# Sheet1.net
KiCad netlist of a schematic drawn in Altium Designer
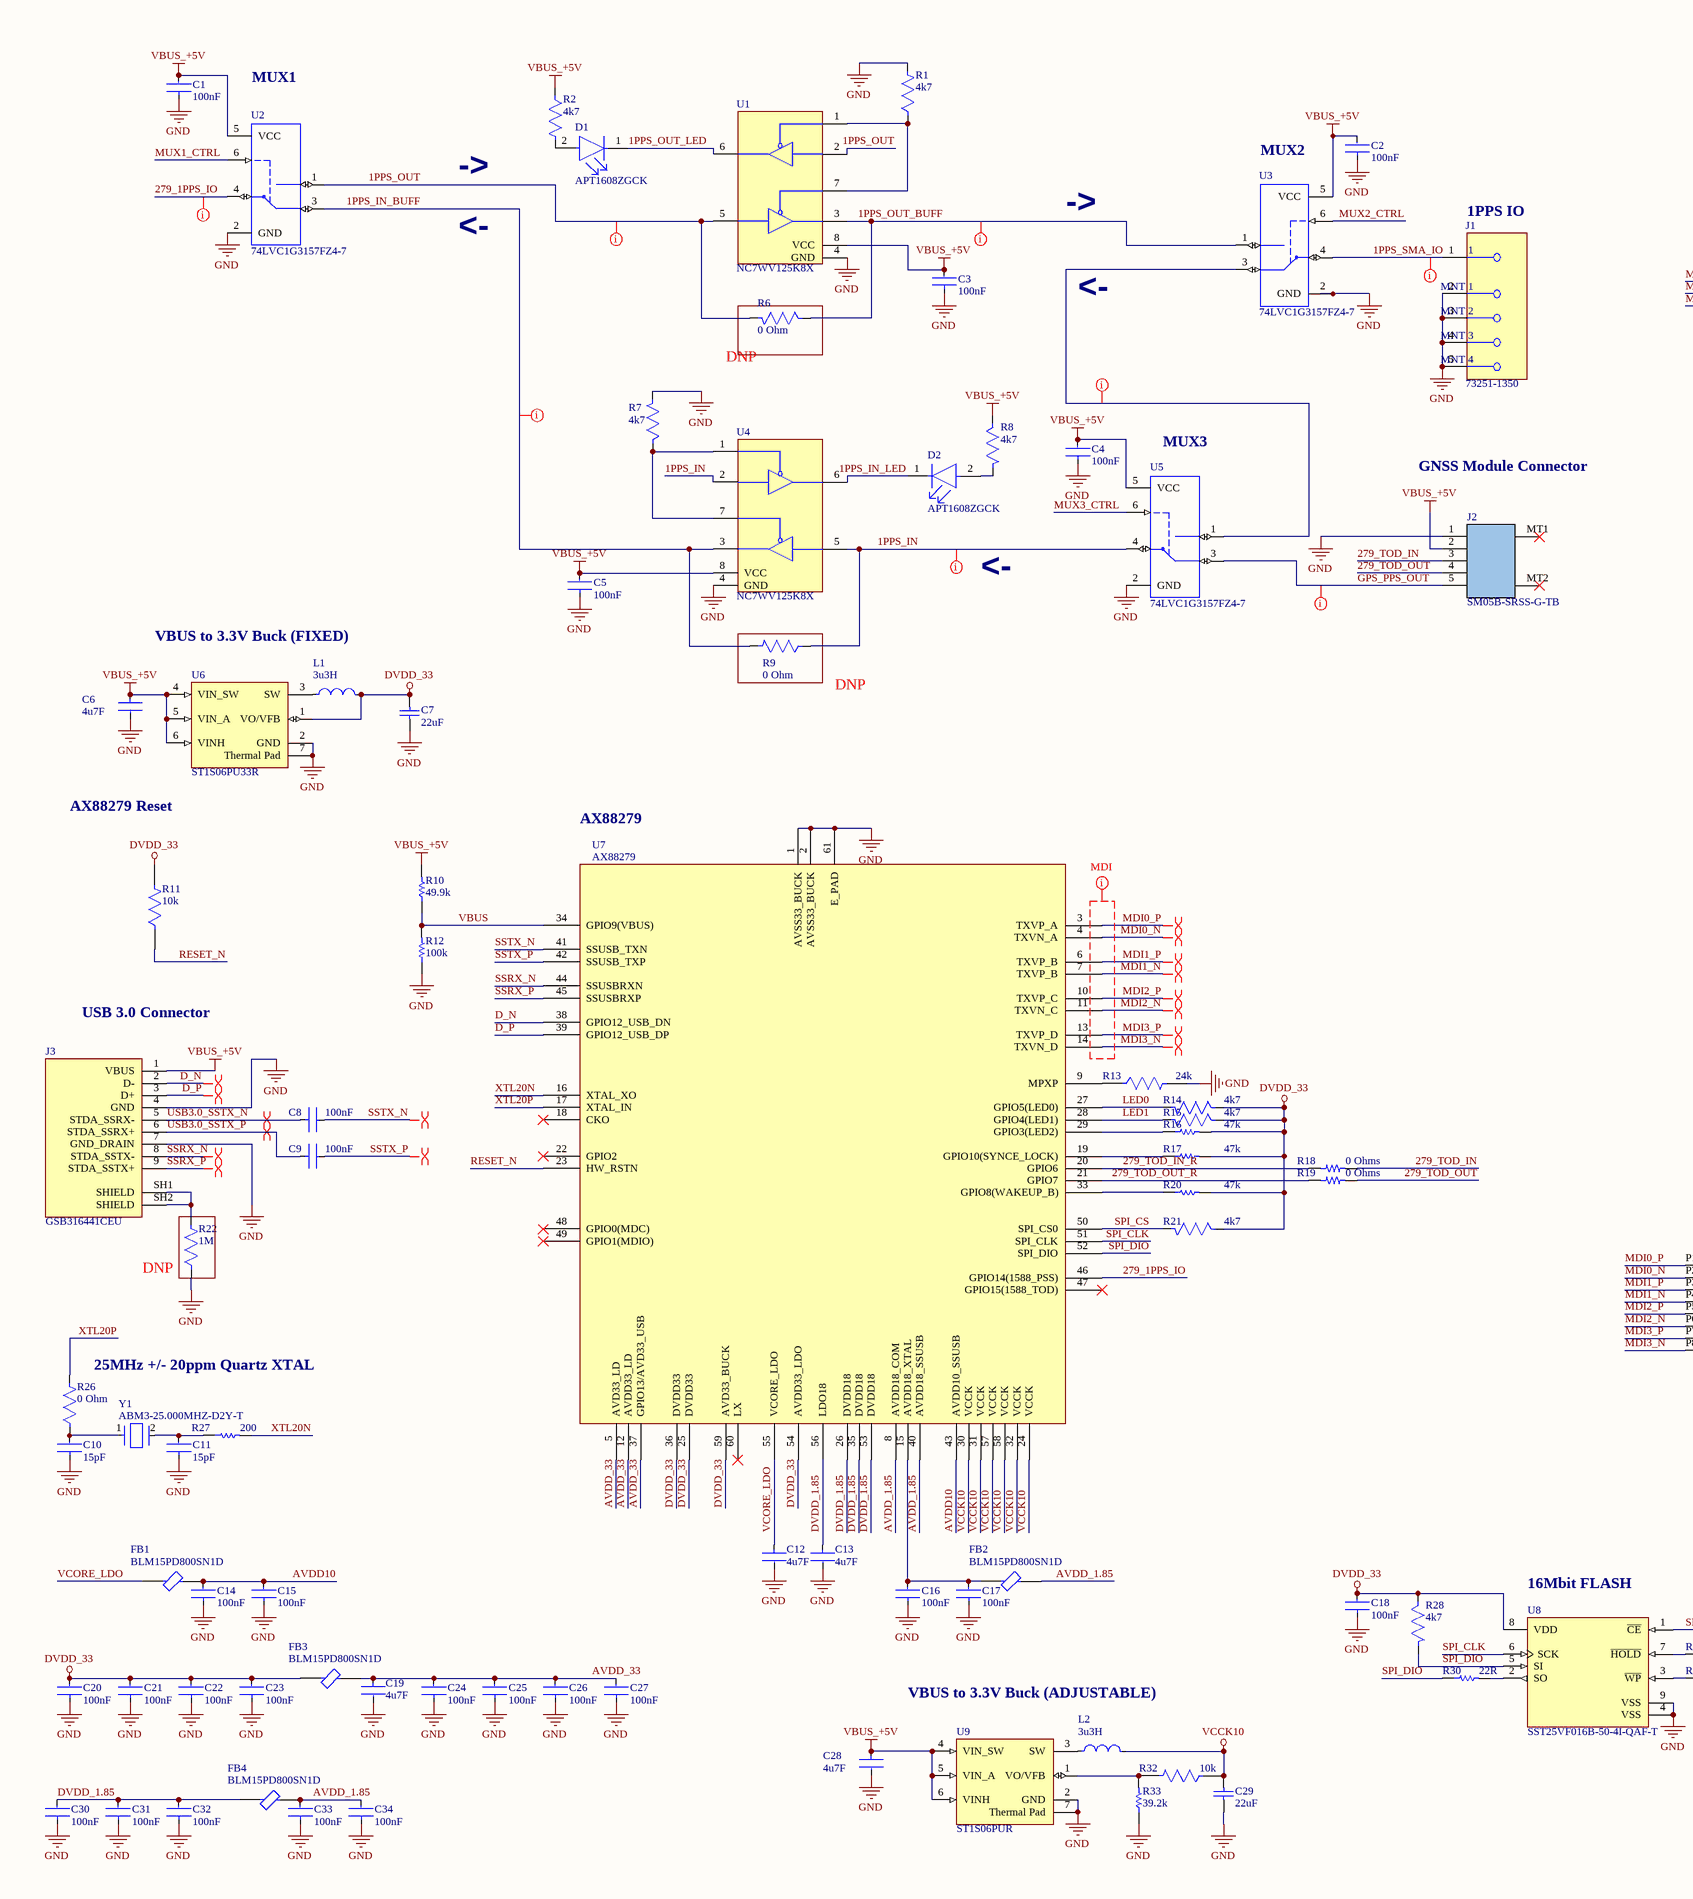
[diagram p0: Sheet1.SchDoc, left]
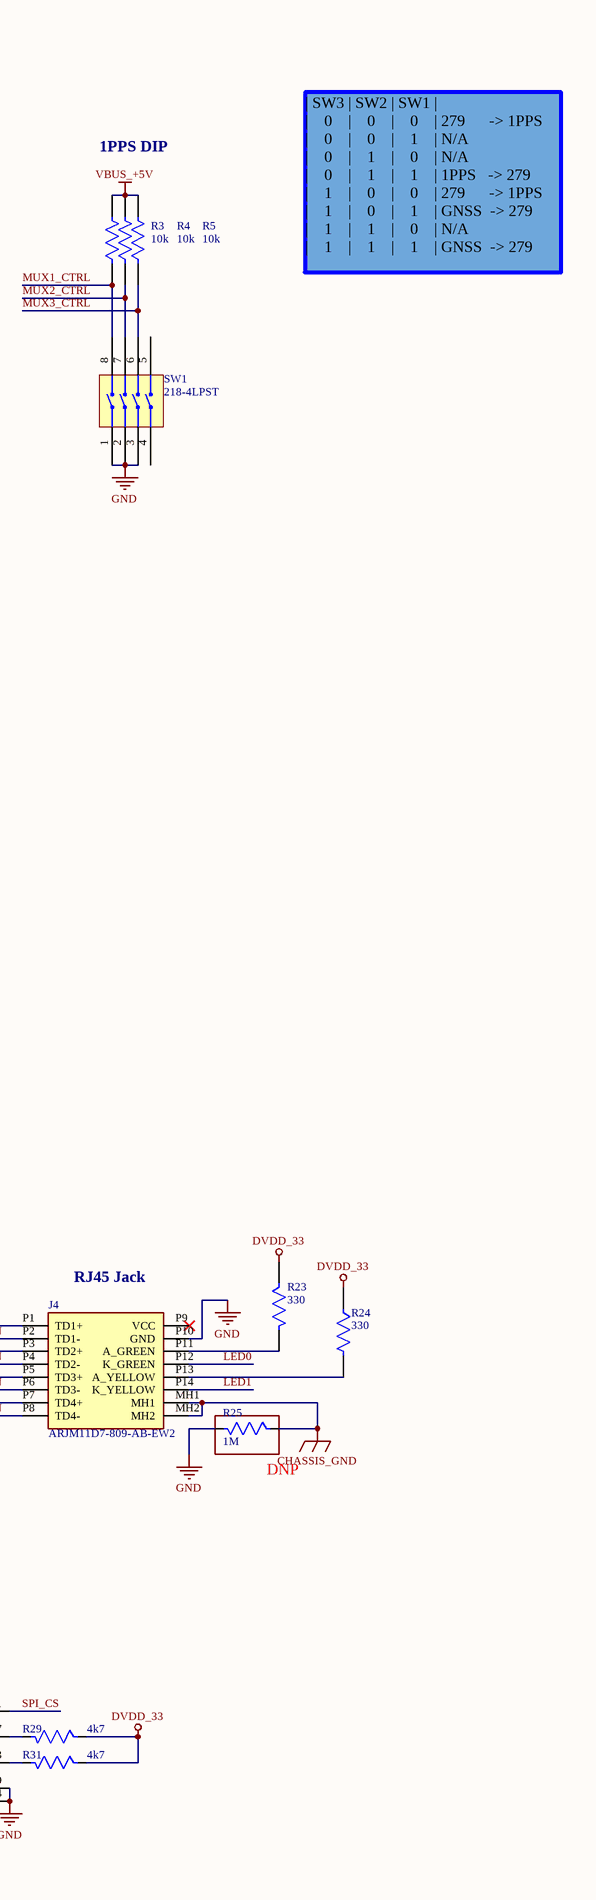
[diagram p1: Sheet1.SchDoc, right]

(export (version "E")
  (design (tool "Eeschema 10.0.6"))
  (components
    (comp (ref "C1")
      (value "100nF")
      (footprint "FP-CL251-IPC_C")
      (description "Cap Ceramic 100nF 10V X7R ±10% SMD 0402 +125°C Paper T/R")
      (fields (field (name "TOLERANCE") "10%") (field (name "MANUFACTURER") "KEMET"))
      (libsource (lib "Altium Content Vault") (part "b4654b650e69147ec39a6b967a45e02"))
    )
    (comp (ref "C2")
      (value "100nF")
      (footprint "FP-CL251-IPC_C")
      (description "Cap Ceramic 100nF 10V X7R ±10% SMD 0402 +125°C Paper T/R")
      (fields (field (name "TOLERANCE") "10%") (field (name "MANUFACTURER") "KEMET"))
      (libsource (lib "Altium Content Vault") (part "b4654b650e69147ec39a6b967a45e02"))
    )
    (comp (ref "C3")
      (value "100nF")
      (footprint "FP-CL251-IPC_C")
      (description "Cap Ceramic 100nF 10V X7R ±10% SMD 0402 +125°C Paper T/R")
      (fields (field (name "TOLERANCE") "10%") (field (name "MANUFACTURER") "KEMET"))
      (libsource (lib "Altium Content Vault") (part "b4654b650e69147ec39a6b967a45e02"))
    )
    (comp (ref "C4")
      (value "100nF")
      (footprint "FP-CL251-IPC_C")
      (description "Cap Ceramic 100nF 10V X7R ±10% SMD 0402 +125°C Paper T/R")
      (fields (field (name "TOLERANCE") "10%") (field (name "MANUFACTURER") "KEMET"))
      (libsource (lib "Altium Content Vault") (part "b4654b650e69147ec39a6b967a45e02"))
    )
    (comp (ref "C5")
      (value "100nF")
      (footprint "FP-CL251-IPC_C")
      (description "Cap Ceramic 100nF 10V X7R ±10% SMD 0402 +125°C Paper T/R")
      (fields (field (name "TOLERANCE") "10%") (field (name "MANUFACTURER") "KEMET"))
      (libsource (lib "Altium Content Vault") (part "b4654b650e69147ec39a6b967a45e02"))
    )
    (comp (ref "C6")
      (value "4u7F")
      (footprint "FP-0402-L_1_0_0_15-W_0_5-IPC_C")
      (description "Ceramic Capacitor General Use 4.7uF ±20% 10V X5R 0402")
      (fields (field (name "TOLERANCE") "20%") (field (name "MANUFACTURER") "Taiyo Yuden"))
      (libsource (lib "Altium Content Vault") (part "236180d848d6139a670b325ea6854c9"))
    )
    (comp (ref "C7")
      (value "22uF")
      (footprint "CAPC1608X100X20ML10")
      (description "Chip Capacitor, 22 uF, +/- 20%, 10 V, -55 to 85 degC, 0603 (1608 Metric), RoHS, Tape and Reel")
      (fields (field (name "MANUFACTURER") "TDK") (field (name "TOLERANCE") "±20%"))
      (libsource (lib "Altium Content Vault") (part "CAP-NP-2"))
    )
    (comp (ref "C8")
      (value "100nF")
      (footprint "FP-CL251-IPC_C")
      (description "Cap Ceramic 100nF 10V X7R ±10% SMD 0402 +125°C Paper T/R")
      (fields (field (name "TOLERANCE") "10%") (field (name "MANUFACTURER") "KEMET"))
      (libsource (lib "Altium Content Vault") (part "b4654b650e69147ec39a6b967a45e02"))
    )
    (comp (ref "C9")
      (value "100nF")
      (footprint "FP-CL251-IPC_C")
      (description "Cap Ceramic 100nF 10V X7R ±10% SMD 0402 +125°C Paper T/R")
      (fields (field (name "TOLERANCE") "10%") (field (name "MANUFACTURER") "KEMET"))
      (libsource (lib "Altium Content Vault") (part "b4654b650e69147ec39a6b967a45e02"))
    )
    (comp (ref "C10")
      (value "15pF")
      (footprint "FP-CBR04C-MFG")
      (description "CAP CER 15PF 100V C0G/NP0 0402")
      (fields
        (field (name "MANUFACTURER") "KEMET")
        (field (name "OCTOPART") "https://octopart.com/cbr04c150f1gac-kemet-30609229")
      )
      (libsource (lib "Altium Content Vault") (part "236180d848d6139a670b325ea6854c9"))
    )
    (comp (ref "C11")
      (value "15pF")
      (footprint "FP-CBR04C-MFG")
      (description "CAP CER 15PF 100V C0G/NP0 0402")
      (fields
        (field (name "MANUFACTURER") "KEMET")
        (field (name "OCTOPART") "https://octopart.com/cbr04c150f1gac-kemet-30609229")
      )
      (libsource (lib "Altium Content Vault") (part "236180d848d6139a670b325ea6854c9"))
    )
    (comp (ref "C12")
      (value "4u7F")
      (footprint "FP-0402-L_1_0_0_15-W_0_5-IPC_C")
      (description "Ceramic Capacitor General Use 4.7uF ±20% 10V X5R 0402")
      (fields (field (name "TOLERANCE") "20%") (field (name "MANUFACTURER") "Taiyo Yuden"))
      (libsource (lib "Altium Content Vault") (part "236180d848d6139a670b325ea6854c9"))
    )
    (comp (ref "C13")
      (value "4u7F")
      (footprint "FP-0402-L_1_0_0_15-W_0_5-IPC_C")
      (description "Ceramic Capacitor General Use 4.7uF ±20% 10V X5R 0402")
      (fields (field (name "TOLERANCE") "20%") (field (name "MANUFACTURER") "Taiyo Yuden"))
      (libsource (lib "Altium Content Vault") (part "236180d848d6139a670b325ea6854c9"))
    )
    (comp (ref "C14")
      (value "100nF")
      (footprint "FP-CL251-IPC_C")
      (description "Cap Ceramic 100nF 10V X7R ±10% SMD 0402 +125°C Paper T/R")
      (fields (field (name "TOLERANCE") "10%") (field (name "MANUFACTURER") "KEMET"))
      (libsource (lib "Altium Content Vault") (part "b4654b650e69147ec39a6b967a45e02"))
    )
    (comp (ref "C15")
      (value "100nF")
      (footprint "FP-CL251-IPC_C")
      (description "Cap Ceramic 100nF 10V X7R ±10% SMD 0402 +125°C Paper T/R")
      (fields (field (name "TOLERANCE") "10%") (field (name "MANUFACTURER") "KEMET"))
      (libsource (lib "Altium Content Vault") (part "b4654b650e69147ec39a6b967a45e02"))
    )
    (comp (ref "C16")
      (value "100nF")
      (footprint "FP-CL251-IPC_C")
      (description "Cap Ceramic 100nF 10V X7R ±10% SMD 0402 +125°C Paper T/R")
      (fields (field (name "TOLERANCE") "10%") (field (name "MANUFACTURER") "KEMET"))
      (libsource (lib "Altium Content Vault") (part "b4654b650e69147ec39a6b967a45e02"))
    )
    (comp (ref "C17")
      (value "100nF")
      (footprint "FP-CL251-IPC_C")
      (description "Cap Ceramic 100nF 10V X7R ±10% SMD 0402 +125°C Paper T/R")
      (fields (field (name "TOLERANCE") "10%") (field (name "MANUFACTURER") "KEMET"))
      (libsource (lib "Altium Content Vault") (part "b4654b650e69147ec39a6b967a45e02"))
    )
    (comp (ref "C18")
      (value "100nF")
      (footprint "FP-CL251-IPC_C")
      (description "Cap Ceramic 100nF 10V X7R ±10% SMD 0402 +125°C Paper T/R")
      (fields (field (name "TOLERANCE") "10%") (field (name "MANUFACTURER") "KEMET"))
      (libsource (lib "Altium Content Vault") (part "b4654b650e69147ec39a6b967a45e02"))
    )
    (comp (ref "C19")
      (value "4u7F")
      (footprint "FP-0402-L_1_0_0_15-W_0_5-IPC_C")
      (description "Ceramic Capacitor General Use 4.7uF ±20% 10V X5R 0402")
      (fields (field (name "TOLERANCE") "20%") (field (name "MANUFACTURER") "Taiyo Yuden"))
      (libsource (lib "Altium Content Vault") (part "236180d848d6139a670b325ea6854c9"))
    )
    (comp (ref "C20")
      (value "100nF")
      (footprint "FP-CL251-IPC_C")
      (description "Cap Ceramic 100nF 10V X7R ±10% SMD 0402 +125°C Paper T/R")
      (fields (field (name "TOLERANCE") "10%") (field (name "MANUFACTURER") "KEMET"))
      (libsource (lib "Altium Content Vault") (part "b4654b650e69147ec39a6b967a45e02"))
    )
    (comp (ref "C21")
      (value "100nF")
      (footprint "FP-CL251-IPC_C")
      (description "Cap Ceramic 100nF 10V X7R ±10% SMD 0402 +125°C Paper T/R")
      (fields (field (name "TOLERANCE") "10%") (field (name "MANUFACTURER") "KEMET"))
      (libsource (lib "Altium Content Vault") (part "b4654b650e69147ec39a6b967a45e02"))
    )
    (comp (ref "C22")
      (value "100nF")
      (footprint "FP-CL251-IPC_C")
      (description "Cap Ceramic 100nF 10V X7R ±10% SMD 0402 +125°C Paper T/R")
      (fields (field (name "TOLERANCE") "10%") (field (name "MANUFACTURER") "KEMET"))
      (libsource (lib "Altium Content Vault") (part "b4654b650e69147ec39a6b967a45e02"))
    )
    (comp (ref "C23")
      (value "100nF")
      (footprint "FP-CL251-IPC_C")
      (description "Cap Ceramic 100nF 10V X7R ±10% SMD 0402 +125°C Paper T/R")
      (fields (field (name "TOLERANCE") "10%") (field (name "MANUFACTURER") "KEMET"))
      (libsource (lib "Altium Content Vault") (part "b4654b650e69147ec39a6b967a45e02"))
    )
    (comp (ref "C24")
      (value "100nF")
      (footprint "FP-CL251-IPC_C")
      (description "Cap Ceramic 100nF 10V X7R ±10% SMD 0402 +125°C Paper T/R")
      (fields (field (name "TOLERANCE") "10%") (field (name "MANUFACTURER") "KEMET"))
      (libsource (lib "Altium Content Vault") (part "b4654b650e69147ec39a6b967a45e02"))
    )
    (comp (ref "C25")
      (value "100nF")
      (footprint "FP-CL251-IPC_C")
      (description "Cap Ceramic 100nF 10V X7R ±10% SMD 0402 +125°C Paper T/R")
      (fields (field (name "TOLERANCE") "10%") (field (name "MANUFACTURER") "KEMET"))
      (libsource (lib "Altium Content Vault") (part "b4654b650e69147ec39a6b967a45e02"))
    )
    (comp (ref "C26")
      (value "100nF")
      (footprint "FP-CL251-IPC_C")
      (description "Cap Ceramic 100nF 10V X7R ±10% SMD 0402 +125°C Paper T/R")
      (fields (field (name "TOLERANCE") "10%") (field (name "MANUFACTURER") "KEMET"))
      (libsource (lib "Altium Content Vault") (part "b4654b650e69147ec39a6b967a45e02"))
    )
    (comp (ref "C27")
      (value "100nF")
      (footprint "FP-CL251-IPC_C")
      (description "Cap Ceramic 100nF 10V X7R ±10% SMD 0402 +125°C Paper T/R")
      (fields (field (name "TOLERANCE") "10%") (field (name "MANUFACTURER") "KEMET"))
      (libsource (lib "Altium Content Vault") (part "b4654b650e69147ec39a6b967a45e02"))
    )
    (comp (ref "C28")
      (value "4u7F")
      (footprint "FP-0402-L_1_0_0_15-W_0_5-IPC_C")
      (description "Ceramic Capacitor General Use 4.7uF ±20% 10V X5R 0402")
      (fields (field (name "TOLERANCE") "20%") (field (name "MANUFACTURER") "Taiyo Yuden"))
      (libsource (lib "Altium Content Vault") (part "236180d848d6139a670b325ea6854c9"))
    )
    (comp (ref "C29")
      (value "22uF")
      (footprint "CAPC1608X100X20ML10")
      (description "Chip Capacitor, 22 uF, +/- 20%, 10 V, -55 to 85 degC, 0603 (1608 Metric), RoHS, Tape and Reel")
      (fields (field (name "MANUFACTURER") "TDK") (field (name "TOLERANCE") "±20%"))
      (libsource (lib "Altium Content Vault") (part "CAP-NP-2"))
    )
    (comp (ref "C30")
      (value "100nF")
      (footprint "FP-CL251-IPC_C")
      (description "Cap Ceramic 100nF 10V X7R ±10% SMD 0402 +125°C Paper T/R")
      (fields (field (name "TOLERANCE") "10%") (field (name "MANUFACTURER") "KEMET"))
      (libsource (lib "Altium Content Vault") (part "b4654b650e69147ec39a6b967a45e02"))
    )
    (comp (ref "C31")
      (value "100nF")
      (footprint "FP-CL251-IPC_C")
      (description "Cap Ceramic 100nF 10V X7R ±10% SMD 0402 +125°C Paper T/R")
      (fields (field (name "TOLERANCE") "10%") (field (name "MANUFACTURER") "KEMET"))
      (libsource (lib "Altium Content Vault") (part "b4654b650e69147ec39a6b967a45e02"))
    )
    (comp (ref "C32")
      (value "100nF")
      (footprint "FP-CL251-IPC_C")
      (description "Cap Ceramic 100nF 10V X7R ±10% SMD 0402 +125°C Paper T/R")
      (fields (field (name "TOLERANCE") "10%") (field (name "MANUFACTURER") "KEMET"))
      (libsource (lib "Altium Content Vault") (part "b4654b650e69147ec39a6b967a45e02"))
    )
    (comp (ref "C33")
      (value "100nF")
      (footprint "FP-CL251-IPC_C")
      (description "Cap Ceramic 100nF 10V X7R ±10% SMD 0402 +125°C Paper T/R")
      (fields (field (name "TOLERANCE") "10%") (field (name "MANUFACTURER") "KEMET"))
      (libsource (lib "Altium Content Vault") (part "b4654b650e69147ec39a6b967a45e02"))
    )
    (comp (ref "C34")
      (value "100nF")
      (footprint "FP-CL251-IPC_C")
      (description "Cap Ceramic 100nF 10V X7R ±10% SMD 0402 +125°C Paper T/R")
      (fields (field (name "TOLERANCE") "10%") (field (name "MANUFACTURER") "KEMET"))
      (libsource (lib "Altium Content Vault") (part "b4654b650e69147ec39a6b967a45e02"))
    )
    (comp (ref "D1")
      (value "APT1608ZGCK")
      (footprint "FP-APT1608ZGCK-MFG")
      (description "LED GREEN CLEAR CHIP SMD")
      (fields (field (name "MANUFACTURER") "Kingbright"))
      (libsource (lib "Altium Content Vault") (part "8706943c75ba83719d021d2fdc84c58"))
    )
    (comp (ref "D2")
      (value "APT1608ZGCK")
      (footprint "FP-APT1608ZGCK-MFG")
      (description "LED GREEN CLEAR CHIP SMD")
      (fields (field (name "MANUFACTURER") "Kingbright"))
      (libsource (lib "Altium Content Vault") (part "8706943c75ba83719d021d2fdc84c58"))
    )
    (comp (ref "FB1")
      (value "BLM15PD800SN1D")
      (footprint "FP-BLM15-0_05-MFG")
      (description "Chip Ferrite Bead, 0402, 80Ω @ 100MHz, 0.07Ω, 25%, 1.5A")
      (fields (field (name "TOLERANCE") "25%") (field (name "MANUFACTURER") "Murata"))
      (libsource (lib "Altium Content Vault") (part "5f30dd21d616792df468990f7003faa"))
    )
    (comp (ref "FB2")
      (value "BLM15PD800SN1D")
      (footprint "FP-BLM15-0_05-MFG")
      (description "Chip Ferrite Bead, 0402, 80Ω @ 100MHz, 0.07Ω, 25%, 1.5A")
      (fields (field (name "TOLERANCE") "25%") (field (name "MANUFACTURER") "Murata"))
      (libsource (lib "Altium Content Vault") (part "5f30dd21d616792df468990f7003faa"))
    )
    (comp (ref "FB3")
      (value "BLM15PD800SN1D")
      (footprint "FP-BLM15-0_05-MFG")
      (description "Chip Ferrite Bead, 0402, 80Ω @ 100MHz, 0.07Ω, 25%, 1.5A")
      (fields (field (name "TOLERANCE") "25%") (field (name "MANUFACTURER") "Murata"))
      (libsource (lib "Altium Content Vault") (part "5f30dd21d616792df468990f7003faa"))
    )
    (comp (ref "FB4")
      (value "BLM15PD800SN1D")
      (footprint "FP-BLM15-0_05-MFG")
      (description "Chip Ferrite Bead, 0402, 80Ω @ 100MHz, 0.07Ω, 25%, 1.5A")
      (fields (field (name "TOLERANCE") "25%") (field (name "MANUFACTURER") "Murata"))
      (libsource (lib "Altium Content Vault") (part "5f30dd21d616792df468990f7003faa"))
    )
    (comp (ref "J1")
      (value "73251-1350")
      (footprint "FP-73251-1350-MFG")
      (description "CONN SMA JACK STR 50 OHM SMD")
      (fields
        (field (name "OCTOPART") "https://octopart.com/73251-1350-molex-5414390")
        (field (name "MANUFACTURER") "Molex")
      )
      (libsource (lib "Altium Content Vault") (part "474d33b8a96b1ade9ed6dd87a2b06d4"))
    )
    (comp (ref "J2")
      (value "JST_SM05B-SRSS-G-TB")
      (footprint "JST_SM05B-SRSS-TB_REV_NOV_29_2010")
      (description "CONN, B2C/W, HEADER, 5-POS, 1.00MM PITCH, 2.90MM H, RA, TIN, SMT")
      (fields
        (field (name "MANUFACTURER") "JST Sales America Inc.")
        (field (name "INTERNAL PART NUMBER") "830-02819-00")
        (field (name "MANUFACTURER PART NUMBER") "SM05B-SRSS-G-TB")
      )
      (libsource (lib "Meta RLR Altium Enterprise Server") (part "CONN_SR_005pin_002mt_M"))
    )
    (comp (ref "J3")
      (value "GSB316441CEU")
      (footprint "CONN_AMPHENOL_GSB316441CEU")
      (description "Conn USB 3.0 Type A PL 9 POS Solder RA SMD 9 Terminal 1 Port")
      (fields (field (name "MF") "Amphenol") (field (name "MANUFACTURER") "Amphenol Commercial"))
      (libsource (lib "LotusSound") (part "CONN_GSB316441CEU"))
    )
    (comp (ref "J4")
      (value "ARJM11D7-809-AB-EW2")
      (footprint "SamacSys:ARJM11D7809ABEW2")
      (description "Connector")
      (fields (field (name "MOUSER PART NUMBER") "815-RJM11D7809ABEW2"))
      (libsource (lib "*") (part "ARJM11D7-809-AB-EW2"))
    )
    (comp (ref "L1")
      (value "3u3H")
      (footprint "FP-LQM2HPN_G0-IPC_A")
      (description "Multilayer Type Inductor for Power Lines, 1008 (2520), 3.3μH, 20%, 0.125Ω, 1.2A")
      (fields (field (name "TOLERANCE") "20%") (field (name "MANUFACTURER") "Murata"))
      (libsource (lib "Altium Content Vault") (part "725321dda6339637d4d059423bc1c3c"))
    )
    (comp (ref "L2")
      (value "3u3H")
      (footprint "FP-LQM2HPN_G0-IPC_A")
      (description "Multilayer Type Inductor for Power Lines, 1008 (2520), 3.3μH, 20%, 0.125Ω, 1.2A")
      (fields (field (name "TOLERANCE") "20%") (field (name "MANUFACTURER") "Murata"))
      (libsource (lib "Altium Content Vault") (part "725321dda6339637d4d059423bc1c3c"))
    )
    (comp (ref "R1")
      (value "4k7")
      (footprint "FP-RT0402-MFG")
      (description "RES SMD 4.7K OHM 0.1% 1/16W 0402")
      (fields
        (field (name "MANUFACTURER") "Yageo")
        (field (name "OCTOPART") "https://octopart.com/rt0402brd074k7l-yageo-1415343")
      )
      (libsource (lib "Altium Content Vault") (part "1029c3af85768c4190bb7ad29bc67b5"))
    )
    (comp (ref "R2")
      (value "4k7")
      (footprint "FP-RT0402-MFG")
      (description "RES SMD 4.7K OHM 0.1% 1/16W 0402")
      (fields
        (field (name "MANUFACTURER") "Yageo")
        (field (name "OCTOPART") "https://octopart.com/rt0402brd074k7l-yageo-1415343")
      )
      (libsource (lib "Altium Content Vault") (part "1029c3af85768c4190bb7ad29bc67b5"))
    )
    (comp (ref "R3")
      (value "10k")
      (footprint "FP-RMCF0402-IPC_C")
      (description "10kΩ ±1% 0.063W 0402 Thick Film Chip Resistor AEC-Q200 compliant")
      (fields (field (name "TOLERANCE") "1%") (field (name "MANUFACTURER") "Stackpole Electronics"))
      (libsource (lib "") (part "1029c3af85768c4190bb7ad29bc67b5_1"))
    )
    (comp (ref "R4")
      (value "10k")
      (footprint "FP-RMCF0402-IPC_C")
      (description "10kΩ ±1% 0.063W 0402 Thick Film Chip Resistor AEC-Q200 compliant")
      (fields (field (name "TOLERANCE") "1%") (field (name "MANUFACTURER") "Stackpole Electronics"))
      (libsource (lib "") (part "1029c3af85768c4190bb7ad29bc67b5_1"))
    )
    (comp (ref "R5")
      (value "10k")
      (footprint "FP-RMCF0402-IPC_C")
      (description "10kΩ ±1% 0.063W 0402 Thick Film Chip Resistor AEC-Q200 compliant")
      (fields (field (name "TOLERANCE") "1%") (field (name "MANUFACTURER") "Stackpole Electronics"))
      (libsource (lib "") (part "1029c3af85768c4190bb7ad29bc67b5_1"))
    )
    (comp (ref "R6")
      (value "0 Ohm")
      (footprint "FP-CR0402-IPC_B")
      (description "Thick Film Chip Resistors 0402 0Ω 0.0625W 5%")
      (fields (field (name "TOLERANCE") "5%") (field (name "MANUFACTURER") "Bourns"))
      (libsource (lib "Altium Content Vault") (part "1029c3af85768c4190bb7ad29bc67b5"))
    )
    (comp (ref "R7")
      (value "4k7")
      (footprint "FP-RT0402-MFG")
      (description "RES SMD 4.7K OHM 0.1% 1/16W 0402")
      (fields
        (field (name "MANUFACTURER") "Yageo")
        (field (name "OCTOPART") "https://octopart.com/rt0402brd074k7l-yageo-1415343")
      )
      (libsource (lib "Altium Content Vault") (part "1029c3af85768c4190bb7ad29bc67b5"))
    )
    (comp (ref "R8")
      (value "4k7")
      (footprint "FP-RT0402-MFG")
      (description "RES SMD 4.7K OHM 0.1% 1/16W 0402")
      (fields
        (field (name "MANUFACTURER") "Yageo")
        (field (name "OCTOPART") "https://octopart.com/rt0402brd074k7l-yageo-1415343")
      )
      (libsource (lib "Altium Content Vault") (part "1029c3af85768c4190bb7ad29bc67b5"))
    )
    (comp (ref "R9")
      (value "0 Ohm")
      (footprint "FP-CR0402-IPC_B")
      (description "Thick Film Chip Resistors 0402 0Ω 0.0625W 5%")
      (fields (field (name "TOLERANCE") "5%") (field (name "MANUFACTURER") "Bourns"))
      (libsource (lib "Altium Content Vault") (part "1029c3af85768c4190bb7ad29bc67b5"))
    )
    (comp (ref "R10")
      (value "49.9k")
      (footprint "RESC1005X40X25LL10T10")
      (fields
        (field (name "MANUFACTURER") "Bourns")
        (field (name "PART NUMBER") "CR0402-FX-4992GLF")
        (field (name "TOLERANCE") "1%")
      )
      (libsource (lib "Altium Content Vault") (part "RES"))
    )
    (comp (ref "R11")
      (value "10k")
      (footprint "FP-RMCF0402-IPC_C")
      (description "10kΩ ±1% 0.063W 0402 Thick Film Chip Resistor AEC-Q200 compliant")
      (fields (field (name "TOLERANCE") "1%") (field (name "MANUFACTURER") "Stackpole Electronics"))
      (libsource (lib "") (part "1029c3af85768c4190bb7ad29bc67b5_1"))
    )
    (comp (ref "R12")
      (value "100k")
      (footprint "RESC1005X40X25ML05T05")
      (fields
        (field (name "PART NUMBER") "CRCW0402100KFKTD")
        (field (name "MANUFACTURER") "Vishay Dale")
        (field (name "TOLERANCE") "1%")
      )
      (libsource (lib "Altium Content Vault") (part "RES"))
    )
    (comp (ref "R13")
      (value "24k")
      (footprint "FP-RT0402-MFG")
      (description "RES SMD 24K OHM 1% 1/16W 0402")
      (fields (field (name "MANUFACTURER PART NUMBER") "RT0402FRE0724KL") (field (name "TOLERANCE") "0.01"))
      (libsource (lib "") (part "1029c3af85768c4190bb7ad29bc67b5_1"))
    )
    (comp (ref "R14")
      (value "4k7")
      (footprint "FP-RT0402-MFG")
      (description "RES SMD 4.7K OHM 0.1% 1/16W 0402")
      (fields
        (field (name "MANUFACTURER") "Yageo")
        (field (name "OCTOPART") "https://octopart.com/rt0402brd074k7l-yageo-1415343")
      )
      (libsource (lib "Altium Content Vault") (part "1029c3af85768c4190bb7ad29bc67b5"))
    )
    (comp (ref "R15")
      (value "4k7")
      (footprint "FP-RT0402-MFG")
      (description "RES SMD 4.7K OHM 0.1% 1/16W 0402")
      (fields
        (field (name "MANUFACTURER") "Yageo")
        (field (name "OCTOPART") "https://octopart.com/rt0402brd074k7l-yageo-1415343")
      )
      (libsource (lib "Altium Content Vault") (part "1029c3af85768c4190bb7ad29bc67b5"))
    )
    (comp (ref "R16")
      (value "47k")
      (footprint "RESC1005X40X25LL10T10")
      (fields
        (field (name "PART NUMBER") "RK73B1ETTP473J")
        (field (name "MANUFACTURER") "KOA Speer")
        (field (name "TOLERANCE") "5%")
      )
      (libsource (lib "Altium Content Vault") (part "RES"))
    )
    (comp (ref "R17")
      (value "47k")
      (footprint "RESC1005X40X25LL10T10")
      (fields
        (field (name "PART NUMBER") "RK73B1ETTP473J")
        (field (name "MANUFACTURER") "KOA Speer")
        (field (name "TOLERANCE") "5%")
      )
      (libsource (lib "Altium Content Vault") (part "RES"))
    )
    (comp (ref "R18")
      (value "0 Ohms")
      (footprint "RES 0402_1005")
      (description "RES SMD 0 OHM JUMPER 1/5W 0402")
      (fields (field (name "PART NUMBER") "CRCW04020000Z0EDHP") (field (name "MANUFACTURER") "Vishay Dale"))
      (libsource (lib "Celestial Altium Library - altium_library") (part "Resistor"))
    )
    (comp (ref "R19")
      (value "0 Ohms")
      (footprint "RES 0402_1005")
      (description "RES SMD 0 OHM JUMPER 1/5W 0402")
      (fields (field (name "PART NUMBER") "CRCW04020000Z0EDHP") (field (name "MANUFACTURER") "Vishay Dale"))
      (libsource (lib "Celestial Altium Library - altium_library") (part "Resistor"))
    )
    (comp (ref "R20")
      (value "47k")
      (footprint "RESC1005X40X25LL10T10")
      (fields
        (field (name "PART NUMBER") "RK73B1ETTP473J")
        (field (name "MANUFACTURER") "KOA Speer")
        (field (name "TOLERANCE") "5%")
      )
      (libsource (lib "Altium Content Vault") (part "RES"))
    )
    (comp (ref "R21")
      (value "4k7")
      (footprint "FP-RT0402-MFG")
      (description "RES SMD 4.7K OHM 0.1% 1/16W 0402")
      (fields
        (field (name "MANUFACTURER") "Yageo")
        (field (name "OCTOPART") "https://octopart.com/rt0402brd074k7l-yageo-1415343")
      )
      (libsource (lib "Altium Content Vault") (part "1029c3af85768c4190bb7ad29bc67b5"))
    )
    (comp (ref "R22")
      (value "1M")
      (footprint "FP-RMCF0402-MFG")
      (description "1MΩ ±5% 0.063W 0402 Thick Film Chip Resistor AEC-Q200 compliant")
      (fields (field (name "TOLERANCE") "5%") (field (name "MANUFACTURER") "Stackpole Electronics"))
      (libsource (lib "Altium Content Vault") (part "1029c3af85768c4190bb7ad29bc67b5"))
    )
    (comp (ref "R23")
      (value "330")
      (footprint "FP-RC1005-IPC_B")
      (description "Res Thick Film 0402 330Ω 1% 0.063W ±100ppm/°C Molded SMD T/R")
      (fields (field (name "TOLERANCE") "1%") (field (name "MANUFACTURER") "Samsung"))
      (libsource (lib "") (part "1029c3af85768c4190bb7ad29bc67b5_1"))
    )
    (comp (ref "R24")
      (value "330")
      (footprint "FP-RC1005-IPC_B")
      (description "Res Thick Film 0402 330Ω 1% 0.063W ±100ppm/°C Molded SMD T/R")
      (fields (field (name "TOLERANCE") "1%") (field (name "MANUFACTURER") "Samsung"))
      (libsource (lib "") (part "1029c3af85768c4190bb7ad29bc67b5_1"))
    )
    (comp (ref "R25")
      (value "1M")
      (footprint "FP-RMCF0402-MFG")
      (description "1MΩ ±5% 0.063W 0402 Thick Film Chip Resistor AEC-Q200 compliant")
      (fields (field (name "TOLERANCE") "5%") (field (name "MANUFACTURER") "Stackpole Electronics"))
      (libsource (lib "Altium Content Vault") (part "1029c3af85768c4190bb7ad29bc67b5"))
    )
    (comp (ref "R26")
      (value "0 Ohm")
      (footprint "FP-CR0402-IPC_B")
      (description "Thick Film Chip Resistors 0402 0Ω 0.0625W 5%")
      (fields (field (name "TOLERANCE") "5%") (field (name "MANUFACTURER") "Bourns"))
      (libsource (lib "Altium Content Vault") (part "1029c3af85768c4190bb7ad29bc67b5"))
    )
    (comp (ref "R27")
      (value "200")
      (footprint "RESC1005X40X25LL10T10")
      (fields
        (field (name "MANUFACTURER") "KOA Speer")
        (field (name "PART NUMBER") "RK73B1ETTP201J")
        (field (name "TOLERANCE") "5%")
      )
      (libsource (lib "Altium Content Vault") (part "RES"))
    )
    (comp (ref "R28")
      (value "4k7")
      (footprint "FP-RT0402-MFG")
      (description "RES SMD 4.7K OHM 0.1% 1/16W 0402")
      (fields
        (field (name "MANUFACTURER") "Yageo")
        (field (name "OCTOPART") "https://octopart.com/rt0402brd074k7l-yageo-1415343")
      )
      (libsource (lib "Altium Content Vault") (part "1029c3af85768c4190bb7ad29bc67b5"))
    )
    (comp (ref "R29")
      (value "4k7")
      (footprint "FP-RT0402-MFG")
      (description "RES SMD 4.7K OHM 0.1% 1/16W 0402")
      (fields
        (field (name "MANUFACTURER") "Yageo")
        (field (name "OCTOPART") "https://octopart.com/rt0402brd074k7l-yageo-1415343")
      )
      (libsource (lib "Altium Content Vault") (part "1029c3af85768c4190bb7ad29bc67b5"))
    )
    (comp (ref "R30")
      (value "22R")
      (footprint "RESC1005X40X25ML05T10")
      (fields
        (field (name "PART NUMBER") "RC0402FR-1322RL")
        (field (name "MANUFACTURER") "Yageo / Phycomp")
        (field (name "TOLERANCE") "1%")
      )
      (libsource (lib "Altium Content Vault") (part "RES"))
    )
    (comp (ref "R31")
      (value "4k7")
      (footprint "FP-RT0402-MFG")
      (description "RES SMD 4.7K OHM 0.1% 1/16W 0402")
      (fields
        (field (name "MANUFACTURER") "Yageo")
        (field (name "OCTOPART") "https://octopart.com/rt0402brd074k7l-yageo-1415343")
      )
      (libsource (lib "Altium Content Vault") (part "1029c3af85768c4190bb7ad29bc67b5"))
    )
    (comp (ref "R32")
      (value "10k")
      (footprint "FP-RMCF0402-IPC_C")
      (description "10kΩ ±1% 0.063W 0402 Thick Film Chip Resistor AEC-Q200 compliant")
      (fields (field (name "TOLERANCE") "1%") (field (name "MANUFACTURER") "Stackpole Electronics"))
      (libsource (lib "") (part "1029c3af85768c4190bb7ad29bc67b5_1"))
    )
    (comp (ref "R33")
      (value "39.2k")
      (footprint "RESC1005X40X25ML05T10")
      (fields
        (field (name "PART NUMBER") "RC0402FR-0739K2L")
        (field (name "MANUFACTURER") "Yageo")
        (field (name "TOLERANCE") "1%")
      )
      (libsource (lib "Altium Content Vault") (part "RES"))
    )
    (comp (ref "SW1")
      (value "218-4LPST")
      (footprint "CTS 218-4LPJ")
      (description "SWITCH SLIDE DIP SPST 25MA 24V")
      (fields (field (name "MANUFACTURER") "CTS Electrocomponents"))
      (libsource (lib "Celestial Altium Library - altium_library") (part "DIP SW 4P"))
    )
    (comp (ref "U1")
      (value "NC7WV125K8X")
      (footprint "SamacSys:SOP50P310X90-8N")
      (description "Integrated Circuit")
      (fields (field (name "MOUSER PART NUMBER") "512-NC7WV125K8X"))
      (libsource (lib "SamacSys") (part "NC7WV125K8X"))
    )
    (comp (ref "U2")
      (value "74LVC1G3157FZ4-7")
      (footprint "PSON50P140X100X40-6N")
      (description "Analog Switch Single SPDT 6-Pin X2-DFN T/R")
      (libsource (lib "74LVC1G3157FZ4-7") (part "74LVC1G3157FZ4-7"))
    )
    (comp (ref "U3")
      (value "74LVC1G3157FZ4-7")
      (footprint "PSON50P140X100X40-6N")
      (description "Analog Switch Single SPDT 6-Pin X2-DFN T/R")
      (libsource (lib "74LVC1G3157FZ4-7") (part "74LVC1G3157FZ4-7"))
    )
    (comp (ref "U4")
      (value "NC7WV125K8X")
      (footprint "SamacSys:SOP50P310X90-8N")
      (description "Integrated Circuit")
      (fields (field (name "MOUSER PART NUMBER") "512-NC7WV125K8X"))
      (libsource (lib "") (part "NC7WV125K8X_1"))
    )
    (comp (ref "U5")
      (value "74LVC1G3157FZ4-7")
      (footprint "PSON50P140X100X40-6N")
      (description "Analog Switch Single SPDT 6-Pin X2-DFN T/R")
      (libsource (lib "74LVC1G3157FZ4-7") (part "74LVC1G3157FZ4-7"))
    )
    (comp (ref "U6")
      (value "ST1S06PU33R")
      (footprint "DFN6D_L")
      (fields (field (name "MANUFACTURER") "STMicroelectronics"))
      (libsource (lib "Altium Content Vault") (part "PM-DCDC-ST1S06-IL7"))
    )
    (comp (ref "U7")
      (value "AX88279")
      (footprint "IC_AX88279")
      (libsource (lib "LotusSound") (part "IC_AX88279"))
    )
    (comp (ref "U8")
      (value "SST25VF016B-50-4I-QAF-T")
      (footprint "FP-C04-452-MFG")
      (libsource (lib "Altium Content Vault") (part "d7313dde12fd16fde488169701056cc"))
    )
    (comp (ref "U9")
      (value "ST1S06PUR")
      (footprint "DFN6D_M")
      (libsource (lib "Altium Content Vault") (part "PM-DCDC-ST1S06-IL7"))
    )
    (comp (ref "Y1")
      (value "ABM3-25.000MHZ-D2Y-T")
      (footprint "FP-ABM3-MFG")
      (description "Crystal 25MHz ±20ppm 18pF SMD-2 5mm x 3.2mm")
      (fields (field (name "TOLERANCE") "20ppm") (field (name "MANUFACTURER") "Abracon"))
      (libsource (lib "Altium Content Vault") (part "c23a69dc6c9e2f18f2079038eb95dd1"))
    )
  )
  (nets
    (net (code "1") (name "/1PPS_IN") (class "Default")
      (node (ref "R9") (pin "1") (pinfunction "1_1") (pintype "passive"))
      (node (ref "U4") (pin "2") (pintype "passive"))
      (node (ref "U4") (pin "5") (pintype "passive"))
      (node (ref "U5") (pin "4") (pinfunction "A_4") (pintype "bidirectional"))
    )
    (net (code "2") (name "/1PPS_IN_BUFF") (class "Default")
      (node (ref "R9") (pin "2") (pinfunction "2_2") (pintype "passive"))
      (node (ref "U2") (pin "3") (pinfunction "B0_3") (pintype "bidirectional"))
      (node (ref "U4") (pin "3") (pintype "passive"))
    )
    (net (code "3") (name "/1PPS_IN_LED") (class "Default")
      (node (ref "D2") (pin "1") (pinfunction "C_1") (pintype "passive"))
      (node (ref "U4") (pin "6") (pintype "passive"))
    )
    (net (code "4") (name "/1PPS_OUT") (class "Default")
      (node (ref "R6") (pin "2") (pinfunction "2_2") (pintype "passive"))
      (node (ref "U1") (pin "2") (pintype "passive"))
      (node (ref "U1") (pin "5") (pintype "passive"))
      (node (ref "U2") (pin "1") (pinfunction "B1_1") (pintype "bidirectional"))
    )
    (net (code "5") (name "/1PPS_OUT_BUFF") (class "Default")
      (node (ref "R6") (pin "1") (pinfunction "1_1") (pintype "passive"))
      (node (ref "U1") (pin "3") (pintype "passive"))
      (node (ref "U3") (pin "1") (pinfunction "B1_1") (pintype "bidirectional"))
    )
    (net (code "6") (name "/1PPS_OUT_LED") (class "Default")
      (node (ref "D1") (pin "1") (pinfunction "C_1") (pintype "passive"))
      (node (ref "U1") (pin "6") (pintype "passive"))
    )
    (net (code "7") (name "/1PPS_SMA_IO") (class "Default")
      (node (ref "J1") (pin "1") (pinfunction "1_1") (pintype "passive"))
      (node (ref "U3") (pin "4") (pinfunction "A_4") (pintype "bidirectional"))
    )
    (net (code "8") (name "/279_1PPS_IO") (class "Default")
      (node (ref "U2") (pin "4") (pinfunction "A_4") (pintype "bidirectional"))
      (node (ref "U7") (pin "46") (pinfunction "GPIO14(1588_PSS)_46") (pintype "passive"))
    )
    (net (code "9") (name "/279_TOD_IN") (class "Default")
      (node (ref "J2") (pin "3") (pinfunction "3_3") (pintype "passive"))
      (node (ref "R18") (pin "2") (pinfunction "2_2") (pintype "passive"))
    )
    (net (code "10") (name "/279_TOD_IN_R") (class "Default")
      (node (ref "R18") (pin "1") (pinfunction "1_1") (pintype "passive"))
      (node (ref "U7") (pin "20") (pinfunction "GPIO6_20") (pintype "passive"))
    )
    (net (code "11") (name "/279_TOD_OUT") (class "Default")
      (node (ref "J2") (pin "4") (pinfunction "4_4") (pintype "passive"))
      (node (ref "R19") (pin "2") (pinfunction "2_2") (pintype "passive"))
    )
    (net (code "12") (name "/279_TOD_OUT_R") (class "Default")
      (node (ref "R19") (pin "1") (pinfunction "1_1") (pintype "passive"))
      (node (ref "U7") (pin "21") (pinfunction "GPIO7_21") (pintype "passive"))
    )
    (net (code "13") (name "/AVDD10") (class "Default")
      (node (ref "C14") (pin "2") (pinfunction "2_2") (pintype "passive"))
      (node (ref "C15") (pin "2") (pinfunction "2_2") (pintype "passive"))
      (node (ref "FB1") (pin "2") (pinfunction "2_2") (pintype "passive"))
      (node (ref "U7") (pin "43") (pinfunction "AVDD10_SSUSB_43") (pintype "passive"))
    )
    (net (code "14") (name "/AVDD_1.85") (class "Default")
      (node (ref "C33") (pin "2") (pinfunction "2_2") (pintype "passive"))
      (node (ref "C34") (pin "2") (pinfunction "2_2") (pintype "passive"))
      (node (ref "FB2") (pin "2") (pinfunction "2_2") (pintype "passive"))
      (node (ref "FB4") (pin "2") (pinfunction "2_2") (pintype "passive"))
      (node (ref "U7") (pin "40") (pinfunction "AVDD18_SSUSB_40") (pintype "passive"))
      (node (ref "U7") (pin "8") (pinfunction "AVDD18_COM_8") (pintype "passive"))
    )
    (net (code "15") (name "/AVDD_33") (class "Default")
      (node (ref "C19") (pin "2") (pinfunction "2_2") (pintype "passive"))
      (node (ref "C24") (pin "2") (pinfunction "2_2") (pintype "passive"))
      (node (ref "C25") (pin "2") (pinfunction "2_2") (pintype "passive"))
      (node (ref "C26") (pin "2") (pinfunction "2_2") (pintype "passive"))
      (node (ref "C27") (pin "2") (pinfunction "2_2") (pintype "passive"))
      (node (ref "FB3") (pin "2") (pinfunction "2_2") (pintype "passive"))
      (node (ref "U7") (pin "12") (pinfunction "AVDD33_LD_12") (pintype "passive"))
      (node (ref "U7") (pin "37") (pinfunction "GPIO13/AVD33_USB_37") (pintype "passive"))
      (node (ref "U7") (pin "5") (pinfunction "AVD33_LD_5") (pintype "passive"))
    )
    (net (code "16") (name "/DVDD_1.85") (class "Default")
      (node (ref "C13") (pin "2") (pinfunction "2_2") (pintype "passive"))
      (node (ref "C30") (pin "2") (pinfunction "2_2") (pintype "passive"))
      (node (ref "C31") (pin "2") (pinfunction "2_2") (pintype "passive"))
      (node (ref "C32") (pin "2") (pinfunction "2_2") (pintype "passive"))
      (node (ref "FB4") (pin "1") (pinfunction "1_1") (pintype "passive"))
      (node (ref "U7") (pin "26") (pinfunction "DVDD18_26") (pintype "passive"))
      (node (ref "U7") (pin "35") (pinfunction "DVDD18_35") (pintype "passive"))
      (node (ref "U7") (pin "53") (pinfunction "DVDD18_53") (pintype "passive"))
      (node (ref "U7") (pin "56") (pinfunction "LDO18_56") (pintype "passive"))
    )
    (net (code "17") (name "/D_N") (class "Default")
      (node (ref "J3") (pin "2") (pinfunction "D-_2") (pintype "passive"))
      (node (ref "U7") (pin "38") (pinfunction "GPIO12_USB_DN_38") (pintype "passive"))
    )
    (net (code "18") (name "/D_P") (class "Default")
      (node (ref "J3") (pin "3") (pinfunction "D+_3") (pintype "passive"))
      (node (ref "U7") (pin "39") (pinfunction "GPIO12_USB_DP_39") (pintype "passive"))
    )
    (net (code "19") (name "/GPS_PPS_OUT") (class "Default")
      (node (ref "J2") (pin "5") (pinfunction "5_5") (pintype "passive"))
      (node (ref "U5") (pin "3") (pinfunction "B0_3") (pintype "bidirectional"))
    )
    (net (code "20") (name "/LED0") (class "Default")
      (node (ref "J4") (pin "P12") (pinfunction "K_GREEN_P12") (pintype "passive"))
      (node (ref "R14") (pin "2") (pinfunction "2_2") (pintype "passive"))
      (node (ref "U7") (pin "27") (pinfunction "GPIO5(LED0)_27") (pintype "passive"))
    )
    (net (code "21") (name "/LED1") (class "Default")
      (node (ref "J4") (pin "P14") (pinfunction "K_YELLOW_P14") (pintype "passive"))
      (node (ref "R15") (pin "2") (pinfunction "2_2") (pintype "passive"))
      (node (ref "U7") (pin "28") (pinfunction "GPIO4(LED1)_28") (pintype "passive"))
    )
    (net (code "22") (name "/MDI0_N") (class "Default")
      (node (ref "J4") (pin "P2") (pinfunction "TD1-_P2") (pintype "passive"))
      (node (ref "U7") (pin "4") (pinfunction "TXVN_A_4") (pintype "passive"))
    )
    (net (code "23") (name "/MDI0_P") (class "Default")
      (node (ref "J4") (pin "P1") (pinfunction "TD1+_P1") (pintype "passive"))
      (node (ref "U7") (pin "3") (pinfunction "TXVP_A_3") (pintype "passive"))
    )
    (net (code "24") (name "/MDI1_N") (class "Default")
      (node (ref "J4") (pin "P4") (pinfunction "TD2-_P4") (pintype "passive"))
      (node (ref "U7") (pin "7") (pinfunction "TXVP_B_7") (pintype "passive"))
    )
    (net (code "25") (name "/MDI1_P") (class "Default")
      (node (ref "J4") (pin "P3") (pinfunction "TD2+_P3") (pintype "passive"))
      (node (ref "U7") (pin "6") (pinfunction "TXVP_B_6") (pintype "passive"))
    )
    (net (code "26") (name "/MDI2_N") (class "Default")
      (node (ref "J4") (pin "P6") (pinfunction "TD3-_P6") (pintype "passive"))
      (node (ref "U7") (pin "11") (pinfunction "TXVN_C_11") (pintype "passive"))
    )
    (net (code "27") (name "/MDI2_P") (class "Default")
      (node (ref "J4") (pin "P5") (pinfunction "TD3+_P5") (pintype "passive"))
      (node (ref "U7") (pin "10") (pinfunction "TXVP_C_10") (pintype "passive"))
    )
    (net (code "28") (name "/MDI3_N") (class "Default")
      (node (ref "J4") (pin "P8") (pinfunction "TD4-_P8") (pintype "passive"))
      (node (ref "U7") (pin "14") (pinfunction "TXVN_D_14") (pintype "passive"))
    )
    (net (code "29") (name "/MDI3_P") (class "Default")
      (node (ref "J4") (pin "P7") (pinfunction "TD4+_P7") (pintype "passive"))
      (node (ref "U7") (pin "13") (pinfunction "TXVP_D_13") (pintype "passive"))
    )
    (net (code "30") (name "/MUX1_CTRL") (class "Default")
      (node (ref "R3") (pin "1") (pinfunction "1_1") (pintype "passive"))
      (node (ref "SW1") (pin "8") (pinfunction "8_8") (pintype "passive"))
      (node (ref "U2") (pin "6") (pinfunction "S_6") (pintype "input"))
    )
    (net (code "31") (name "/MUX2_CTRL") (class "Default")
      (node (ref "R4") (pin "1") (pinfunction "1_1") (pintype "passive"))
      (node (ref "SW1") (pin "7") (pinfunction "7_7") (pintype "passive"))
      (node (ref "U3") (pin "6") (pinfunction "S_6") (pintype "input"))
    )
    (net (code "32") (name "/MUX3_CTRL") (class "Default")
      (node (ref "R5") (pin "1") (pinfunction "1_1") (pintype "passive"))
      (node (ref "SW1") (pin "6") (pinfunction "6_6") (pintype "passive"))
      (node (ref "U5") (pin "6") (pinfunction "S_6") (pintype "input"))
    )
    (net (code "33") (name "/RESET_N") (class "Default")
      (node (ref "R11") (pin "1") (pinfunction "1_1") (pintype "passive"))
      (node (ref "U7") (pin "23") (pinfunction "HW_RSTN_23") (pintype "passive"))
    )
    (net (code "34") (name "/SPI_CLK") (class "Default")
      (node (ref "U7") (pin "51") (pinfunction "SPI_CLK_51") (pintype "passive"))
      (node (ref "U8") (pin "6") (pinfunction "SCK_6") (pintype "input"))
    )
    (net (code "35") (name "/SPI_CS") (class "Default")
      (node (ref "R21") (pin "2") (pinfunction "2_2") (pintype "passive"))
      (node (ref "U7") (pin "50") (pinfunction "SPI_CS0_50") (pintype "passive"))
      (node (ref "U8") (pin "1") (pinfunction "~{CE}_1") (pintype "input"))
    )
    (net (code "36") (name "/SPI_DIO") (class "Default")
      (node (ref "R28") (pin "2") (pinfunction "2_2") (pintype "passive"))
      (node (ref "R30") (pin "1") (pinfunction "1_1") (pintype "passive"))
      (node (ref "U7") (pin "52") (pinfunction "SPI_DIO_52") (pintype "passive"))
      (node (ref "U8") (pin "5") (pinfunction "SI_5") (pintype "input"))
    )
    (net (code "37") (name "/SSRX_N") (class "Default")
      (node (ref "J3") (pin "8") (pinfunction "STDA_SSTX-_8") (pintype "passive"))
      (node (ref "U7") (pin "44") (pinfunction "SSUSBRXN_44") (pintype "passive"))
    )
    (net (code "38") (name "/SSRX_P") (class "Default")
      (node (ref "J3") (pin "9") (pinfunction "STDA_SSTX+_9") (pintype "passive"))
      (node (ref "U7") (pin "45") (pinfunction "SSUSBRXP_45") (pintype "passive"))
    )
    (net (code "39") (name "/SSTX_N") (class "Default")
      (node (ref "C8") (pin "2") (pinfunction "2_2") (pintype "passive"))
      (node (ref "U7") (pin "41") (pinfunction "SSUSB_TXN_41") (pintype "passive"))
    )
    (net (code "40") (name "/SSTX_P") (class "Default")
      (node (ref "C9") (pin "2") (pinfunction "2_2") (pintype "passive"))
      (node (ref "U7") (pin "42") (pinfunction "SSUSB_TXP_42") (pintype "passive"))
    )
    (net (code "41") (name "/USB3.0_SSTX_N") (class "Default")
      (node (ref "C8") (pin "1") (pinfunction "1_1") (pintype "passive"))
      (node (ref "J3") (pin "5") (pinfunction "STDA_SSRX-_5") (pintype "passive"))
    )
    (net (code "42") (name "/USB3.0_SSTX_P") (class "Default")
      (node (ref "C9") (pin "1") (pinfunction "1_1") (pintype "passive"))
      (node (ref "J3") (pin "6") (pinfunction "STDA_SSRX+_6") (pintype "passive"))
    )
    (net (code "43") (name "/VBUS") (class "Default")
      (node (ref "R10") (pin "1") (pinfunction "1_1") (pintype "passive"))
      (node (ref "R12") (pin "2") (pinfunction "2_2") (pintype "passive"))
      (node (ref "U7") (pin "34") (pinfunction "GPIO9(VBUS)_34") (pintype "passive"))
    )
    (net (code "44") (name "/VCORE_LDO") (class "Default")
      (node (ref "C12") (pin "2") (pinfunction "2_2") (pintype "passive"))
      (node (ref "FB1") (pin "1") (pinfunction "1_1") (pintype "passive"))
      (node (ref "U7") (pin "55") (pinfunction "VCORE_LDO_55") (pintype "passive"))
    )
    (net (code "45") (name "/XTL20N") (class "Default")
      (node (ref "R27") (pin "2") (pinfunction "2_2") (pintype "passive"))
      (node (ref "U7") (pin "16") (pinfunction "XTAL_XO_16") (pintype "passive"))
    )
    (net (code "46") (name "/XTL20P") (class "Default")
      (node (ref "R26") (pin "2") (pinfunction "2_2") (pintype "passive"))
      (node (ref "U7") (pin "17") (pinfunction "XTAL_IN_17") (pintype "passive"))
    )
    (net (code "47") (name "CHASSIS_GND") (class "Default")
      (node (ref "J4") (pin "MH1") (pinfunction "MH1_MH1") (pintype "passive"))
      (node (ref "J4") (pin "MH2") (pinfunction "MH2_MH2") (pintype "passive"))
      (node (ref "R25") (pin "1") (pinfunction "1_1") (pintype "passive"))
    )
    (net (code "48") (name "DVDD_33") (class "Default")
      (node (ref "C18") (pin "2") (pinfunction "2_2") (pintype "passive"))
      (node (ref "C20") (pin "2") (pinfunction "2_2") (pintype "passive"))
      (node (ref "C21") (pin "2") (pinfunction "2_2") (pintype "passive"))
      (node (ref "C22") (pin "2") (pinfunction "2_2") (pintype "passive"))
      (node (ref "C23") (pin "2") (pinfunction "2_2") (pintype "passive"))
      (node (ref "C7") (pin "2") (pinfunction "2_2") (pintype "passive"))
      (node (ref "FB3") (pin "1") (pinfunction "1_1") (pintype "passive"))
      (node (ref "L1") (pin "2") (pinfunction "2_2") (pintype "passive"))
      (node (ref "R11") (pin "2") (pinfunction "2_2") (pintype "passive"))
      (node (ref "R14") (pin "1") (pinfunction "1_1") (pintype "passive"))
      (node (ref "R15") (pin "1") (pinfunction "1_1") (pintype "passive"))
      (node (ref "R16") (pin "2") (pinfunction "2_2") (pintype "passive"))
      (node (ref "R17") (pin "2") (pinfunction "2_2") (pintype "passive"))
      (node (ref "R20") (pin "2") (pinfunction "2_2") (pintype "passive"))
      (node (ref "R21") (pin "1") (pinfunction "1_1") (pintype "passive"))
      (node (ref "R23") (pin "1") (pinfunction "1_1") (pintype "passive"))
      (node (ref "R24") (pin "1") (pinfunction "1_1") (pintype "passive"))
      (node (ref "R28") (pin "1") (pinfunction "1_1") (pintype "passive"))
      (node (ref "R29") (pin "1") (pinfunction "1_1") (pintype "passive"))
      (node (ref "R31") (pin "1") (pinfunction "1_1") (pintype "passive"))
      (node (ref "U6") (pin "1") (pinfunction "VO/VFB_1") (pintype "bidirectional"))
      (node (ref "U7") (pin "25") (pinfunction "DVDD33_25") (pintype "passive"))
      (node (ref "U7") (pin "36") (pinfunction "DVDD33_36") (pintype "passive"))
      (node (ref "U7") (pin "54") (pinfunction "AVDD33_LDO_54") (pintype "passive"))
      (node (ref "U7") (pin "59") (pinfunction "AVD33_BUCK_59") (pintype "passive"))
      (node (ref "U8") (pin "8") (pinfunction "VDD_8") (pintype "power_in"))
    )
    (net (code "49") (name "GND") (class "Default")
      (node (ref "C1") (pin "1") (pinfunction "1_1") (pintype "passive"))
      (node (ref "C10") (pin "2") (pinfunction "2_2") (pintype "passive"))
      (node (ref "C11") (pin "2") (pinfunction "2_2") (pintype "passive"))
      (node (ref "C12") (pin "1") (pinfunction "1_1") (pintype "passive"))
      (node (ref "C13") (pin "1") (pinfunction "1_1") (pintype "passive"))
      (node (ref "C14") (pin "1") (pinfunction "1_1") (pintype "passive"))
      (node (ref "C15") (pin "1") (pinfunction "1_1") (pintype "passive"))
      (node (ref "C16") (pin "1") (pinfunction "1_1") (pintype "passive"))
      (node (ref "C17") (pin "1") (pinfunction "1_1") (pintype "passive"))
      (node (ref "C18") (pin "1") (pinfunction "1_1") (pintype "passive"))
      (node (ref "C19") (pin "1") (pinfunction "1_1") (pintype "passive"))
      (node (ref "C2") (pin "1") (pinfunction "1_1") (pintype "passive"))
      (node (ref "C20") (pin "1") (pinfunction "1_1") (pintype "passive"))
      (node (ref "C21") (pin "1") (pinfunction "1_1") (pintype "passive"))
      (node (ref "C22") (pin "1") (pinfunction "1_1") (pintype "passive"))
      (node (ref "C23") (pin "1") (pinfunction "1_1") (pintype "passive"))
      (node (ref "C24") (pin "1") (pinfunction "1_1") (pintype "passive"))
      (node (ref "C25") (pin "1") (pinfunction "1_1") (pintype "passive"))
      (node (ref "C26") (pin "1") (pinfunction "1_1") (pintype "passive"))
      (node (ref "C27") (pin "1") (pinfunction "1_1") (pintype "passive"))
      (node (ref "C28") (pin "1") (pinfunction "1_1") (pintype "passive"))
      (node (ref "C29") (pin "1") (pinfunction "1_1") (pintype "passive"))
      (node (ref "C3") (pin "1") (pinfunction "1_1") (pintype "passive"))
      (node (ref "C30") (pin "1") (pinfunction "1_1") (pintype "passive"))
      (node (ref "C31") (pin "1") (pinfunction "1_1") (pintype "passive"))
      (node (ref "C32") (pin "1") (pinfunction "1_1") (pintype "passive"))
      (node (ref "C33") (pin "1") (pinfunction "1_1") (pintype "passive"))
      (node (ref "C34") (pin "1") (pinfunction "1_1") (pintype "passive"))
      (node (ref "C4") (pin "1") (pinfunction "1_1") (pintype "passive"))
      (node (ref "C5") (pin "1") (pinfunction "1_1") (pintype "passive"))
      (node (ref "C6") (pin "1") (pinfunction "1_1") (pintype "passive"))
      (node (ref "C7") (pin "1") (pinfunction "1_1") (pintype "passive"))
      (node (ref "J1") (pin "2") (pinfunction "MNT_1_2") (pintype "passive"))
      (node (ref "J1") (pin "3") (pinfunction "MNT_2_3") (pintype "passive"))
      (node (ref "J1") (pin "4") (pinfunction "MNT_3_4") (pintype "passive"))
      (node (ref "J1") (pin "5") (pinfunction "MNT_4_5") (pintype "passive"))
      (node (ref "J2") (pin "1") (pinfunction "1_1") (pintype "passive"))
      (node (ref "J3") (pin "4") (pinfunction "GND_4") (pintype "power_in"))
      (node (ref "J3") (pin "7") (pinfunction "GND_DRAIN_7") (pintype "power_in"))
      (node (ref "J4") (pin "P10") (pinfunction "GND_P10") (pintype "passive"))
      (node (ref "R1") (pin "2") (pinfunction "2_2") (pintype "passive"))
      (node (ref "R12") (pin "1") (pinfunction "1_1") (pintype "passive"))
      (node (ref "R13") (pin "2") (pinfunction "2_2") (pintype "passive"))
      (node (ref "R22") (pin "1") (pinfunction "1_1") (pintype "passive"))
      (node (ref "R25") (pin "2") (pinfunction "2_2") (pintype "passive"))
      (node (ref "R33") (pin "1") (pinfunction "1_1") (pintype "passive"))
      (node (ref "R7") (pin "2") (pinfunction "2_2") (pintype "passive"))
      (node (ref "SW1") (pin "1") (pinfunction "GND_1") (pintype "passive"))
      (node (ref "SW1") (pin "2") (pinfunction "GND_2") (pintype "passive"))
      (node (ref "SW1") (pin "3") (pinfunction "GND_3") (pintype "passive"))
      (node (ref "U1") (pin "4") (pinfunction "GND_4") (pintype "passive"))
      (node (ref "U2") (pin "2") (pinfunction "GND_2") (pintype "power_in"))
      (node (ref "U3") (pin "2") (pinfunction "GND_2") (pintype "power_in"))
      (node (ref "U4") (pin "4") (pinfunction "GND_4") (pintype "passive"))
      (node (ref "U5") (pin "2") (pinfunction "GND_2") (pintype "power_in"))
      (node (ref "U6") (pin "2") (pinfunction "GND_2") (pintype "power_in"))
      (node (ref "U6") (pin "7") (pinfunction "Thermal_Pad_7") (pintype "power_in"))
      (node (ref "U7") (pin "1") (pinfunction "AVSS33_BUCK_1") (pintype "passive"))
      (node (ref "U7") (pin "2") (pinfunction "AVSS33_BUCK_2") (pintype "passive"))
      (node (ref "U7") (pin "61") (pinfunction "E_PAD_61") (pintype "passive"))
      (node (ref "U8") (pin "4") (pinfunction "VSS_4") (pintype "power_in"))
      (node (ref "U8") (pin "9") (pinfunction "VSS_9") (pintype "power_in"))
      (node (ref "U9") (pin "2") (pinfunction "GND_2") (pintype "power_in"))
      (node (ref "U9") (pin "7") (pinfunction "Thermal_Pad_7") (pintype "power_in"))
    )
    (net (code "50") (name "Net-(C10-Pad1)") (class "Default")
      (node (ref "C10") (pin "1") (pinfunction "1_1") (pintype "passive"))
      (node (ref "R26") (pin "1") (pinfunction "1_1") (pintype "passive"))
      (node (ref "Y1") (pin "1") (pinfunction "1_1") (pintype "passive"))
    )
    (net (code "51") (name "Net-(C11-Pad1)") (class "Default")
      (node (ref "C11") (pin "1") (pinfunction "1_1") (pintype "passive"))
      (node (ref "R27") (pin "1") (pinfunction "1_1") (pintype "passive"))
      (node (ref "Y1") (pin "2") (pinfunction "2_2") (pintype "passive"))
    )
    (net (code "52") (name "Net-(D1-A)") (class "Default")
      (node (ref "D1") (pin "2") (pinfunction "A_2") (pintype "passive"))
      (node (ref "R2") (pin "2") (pinfunction "2_2") (pintype "passive"))
    )
    (net (code "53") (name "Net-(D2-A)") (class "Default")
      (node (ref "D2") (pin "2") (pinfunction "A_2") (pintype "passive"))
      (node (ref "R8") (pin "2") (pinfunction "2_2") (pintype "passive"))
    )
    (net (code "54") (name "Net-(J3-SHIELD-PadSH1)") (class "Default")
      (node (ref "J3") (pin "SH1") (pinfunction "SHIELD_SH1") (pintype "passive"))
      (node (ref "J3") (pin "SH2") (pinfunction "SHIELD_SH2") (pintype "passive"))
      (node (ref "R22") (pin "2") (pinfunction "2_2") (pintype "passive"))
    )
    (net (code "55") (name "Net-(J4-A_GREEN)") (class "Default")
      (node (ref "J4") (pin "P11") (pinfunction "A_GREEN_P11") (pintype "passive"))
      (node (ref "R23") (pin "2") (pinfunction "2_2") (pintype "passive"))
    )
    (net (code "56") (name "Net-(J4-A_YELLOW)") (class "Default")
      (node (ref "J4") (pin "P13") (pinfunction "A_YELLOW_P13") (pintype "passive"))
      (node (ref "R24") (pin "2") (pinfunction "2_2") (pintype "passive"))
    )
    (net (code "57") (name "Net-(R1-Pad1)") (class "Default")
      (node (ref "R1") (pin "1") (pinfunction "1_1") (pintype "passive"))
      (node (ref "U1") (pin "1") (pintype "passive"))
      (node (ref "U1") (pin "7") (pintype "passive"))
    )
    (net (code "58") (name "Net-(R7-Pad1)") (class "Default")
      (node (ref "R7") (pin "1") (pinfunction "1_1") (pintype "passive"))
      (node (ref "U4") (pin "1") (pintype "passive"))
      (node (ref "U4") (pin "7") (pintype "passive"))
    )
    (net (code "59") (name "Net-(U3-B0)") (class "Default")
      (node (ref "U3") (pin "3") (pinfunction "B0_3") (pintype "bidirectional"))
      (node (ref "U5") (pin "1") (pinfunction "B1_1") (pintype "bidirectional"))
    )
    (net (code "60") (name "Net-(U6-SW)") (class "Default")
      (node (ref "L1") (pin "1") (pinfunction "1_1") (pintype "passive"))
      (node (ref "U6") (pin "3") (pinfunction "SW_3") (pintype "passive"))
    )
    (net (code "61") (name "Net-(U7-AVDD18_XTAL)") (class "Default")
      (node (ref "C16") (pin "2") (pinfunction "2_2") (pintype "passive"))
      (node (ref "C17") (pin "2") (pinfunction "2_2") (pintype "passive"))
      (node (ref "FB2") (pin "1") (pinfunction "1_1") (pintype "passive"))
      (node (ref "U7") (pin "15") (pinfunction "AVDD18_XTAL_15") (pintype "passive"))
    )
    (net (code "62") (name "Net-(U7-GPIO3(LED2))") (class "Default")
      (node (ref "R16") (pin "1") (pinfunction "1_1") (pintype "passive"))
      (node (ref "U7") (pin "29") (pinfunction "GPIO3(LED2)_29") (pintype "passive"))
    )
    (net (code "63") (name "Net-(U7-GPIO8(WAKEUP_B))") (class "Default")
      (node (ref "R20") (pin "1") (pinfunction "1_1") (pintype "passive"))
      (node (ref "U7") (pin "33") (pinfunction "GPIO8(WAKEUP_B)_33") (pintype "passive"))
    )
    (net (code "64") (name "Net-(U7-GPIO10(SYNCE_LOCK))") (class "Default")
      (node (ref "R17") (pin "1") (pinfunction "1_1") (pintype "passive"))
      (node (ref "U7") (pin "19") (pinfunction "GPIO10(SYNCE_LOCK)_19") (pintype "passive"))
    )
    (net (code "65") (name "Net-(U7-MPXP)") (class "Default")
      (node (ref "R13") (pin "1") (pinfunction "1_1") (pintype "passive"))
      (node (ref "U7") (pin "9") (pinfunction "MPXP_9") (pintype "passive"))
    )
    (net (code "66") (name "Net-(U8-SO)") (class "Default")
      (node (ref "R30") (pin "2") (pinfunction "2_2") (pintype "passive"))
      (node (ref "U8") (pin "2") (pinfunction "SO_2") (pintype "output"))
    )
    (net (code "67") (name "Net-(U8-~{HOLD})") (class "Default")
      (node (ref "R29") (pin "2") (pinfunction "2_2") (pintype "passive"))
      (node (ref "U8") (pin "7") (pinfunction "~{HOLD}_7") (pintype "input"))
    )
    (net (code "68") (name "Net-(U8-~{WP})") (class "Default")
      (node (ref "R31") (pin "2") (pinfunction "2_2") (pintype "passive"))
      (node (ref "U8") (pin "3") (pinfunction "~{WP}_3") (pintype "input"))
    )
    (net (code "69") (name "Net-(U9-SW)") (class "Default")
      (node (ref "L2") (pin "1") (pinfunction "1_1") (pintype "passive"))
      (node (ref "U9") (pin "3") (pinfunction "SW_3") (pintype "passive"))
    )
    (net (code "70") (name "Net-(U9-VO{slash}VFB)") (class "Default")
      (node (ref "R32") (pin "2") (pinfunction "2_2") (pintype "passive"))
      (node (ref "R33") (pin "2") (pinfunction "2_2") (pintype "passive"))
      (node (ref "U9") (pin "1") (pinfunction "VO/VFB_1") (pintype "bidirectional"))
    )
    (net (code "71") (name "VBUS_+5V") (class "Default")
      (node (ref "C1") (pin "2") (pinfunction "2_2") (pintype "passive"))
      (node (ref "C2") (pin "2") (pinfunction "2_2") (pintype "passive"))
      (node (ref "C28") (pin "2") (pinfunction "2_2") (pintype "passive"))
      (node (ref "C3") (pin "2") (pinfunction "2_2") (pintype "passive"))
      (node (ref "C4") (pin "2") (pinfunction "2_2") (pintype "passive"))
      (node (ref "C5") (pin "2") (pinfunction "2_2") (pintype "passive"))
      (node (ref "C6") (pin "2") (pinfunction "2_2") (pintype "passive"))
      (node (ref "J2") (pin "2") (pinfunction "2_2") (pintype "passive"))
      (node (ref "J3") (pin "1") (pinfunction "VBUS_1") (pintype "power_in"))
      (node (ref "R10") (pin "2") (pinfunction "2_2") (pintype "passive"))
      (node (ref "R2") (pin "1") (pinfunction "1_1") (pintype "passive"))
      (node (ref "R3") (pin "2") (pinfunction "2_2") (pintype "passive"))
      (node (ref "R4") (pin "2") (pinfunction "2_2") (pintype "passive"))
      (node (ref "R5") (pin "2") (pinfunction "2_2") (pintype "passive"))
      (node (ref "R8") (pin "1") (pinfunction "1_1") (pintype "passive"))
      (node (ref "U1") (pin "8") (pinfunction "VCC_8") (pintype "passive"))
      (node (ref "U2") (pin "5") (pinfunction "VCC_5") (pintype "power_in"))
      (node (ref "U3") (pin "5") (pinfunction "VCC_5") (pintype "power_in"))
      (node (ref "U4") (pin "8") (pinfunction "VCC_8") (pintype "passive"))
      (node (ref "U5") (pin "5") (pinfunction "VCC_5") (pintype "power_in"))
      (node (ref "U6") (pin "4") (pinfunction "VIN_SW_4") (pintype "input"))
      (node (ref "U6") (pin "5") (pinfunction "VIN_A_5") (pintype "input"))
      (node (ref "U6") (pin "6") (pinfunction "VINH_6") (pintype "input"))
      (node (ref "U9") (pin "4") (pinfunction "VIN_SW_4") (pintype "input"))
      (node (ref "U9") (pin "5") (pinfunction "VIN_A_5") (pintype "input"))
      (node (ref "U9") (pin "6") (pinfunction "VINH_6") (pintype "input"))
    )
    (net (code "72") (name "VCCK10") (class "Default")
      (node (ref "C29") (pin "2") (pinfunction "2_2") (pintype "passive"))
      (node (ref "L2") (pin "2") (pinfunction "2_2") (pintype "passive"))
      (node (ref "R32") (pin "1") (pinfunction "1_1") (pintype "passive"))
      (node (ref "U7") (pin "24") (pinfunction "VCCK_24") (pintype "passive"))
      (node (ref "U7") (pin "30") (pinfunction "VCCK_30") (pintype "passive"))
      (node (ref "U7") (pin "31") (pinfunction "VCCK_31") (pintype "passive"))
      (node (ref "U7") (pin "32") (pinfunction "VCCK_32") (pintype "passive"))
      (node (ref "U7") (pin "57") (pinfunction "VCCK_57") (pintype "passive"))
      (node (ref "U7") (pin "58") (pinfunction "VCCK_58") (pintype "passive"))
    )
    (net (code "73") (name "unconnected-(J2-PadMT1)") (class "Default")
      (node (ref "J2") (pin "MT1") (pinfunction "MT1_MT1") (pintype "passive+no_connect"))
    )
    (net (code "74") (name "unconnected-(J2-PadMT2)") (class "Default")
      (node (ref "J2") (pin "MT2") (pinfunction "MT2_MT2") (pintype "passive+no_connect"))
    )
    (net (code "75") (name "unconnected-(J4-VCC-PadP9)") (class "Default")
      (node (ref "J4") (pin "P9") (pinfunction "VCC_P9") (pintype "passive+no_connect"))
    )
    (net (code "76") (name "unconnected-(SW1-GND-Pad4)") (class "Default")
      (node (ref "SW1") (pin "4") (pinfunction "GND_4") (pintype "passive"))
    )
    (net (code "77") (name "unconnected-(SW1-Pad5)") (class "Default")
      (node (ref "SW1") (pin "5") (pinfunction "5_5") (pintype "passive"))
    )
    (net (code "78") (name "unconnected-(U7-CKO-Pad18)") (class "Default")
      (node (ref "U7") (pin "18") (pinfunction "CKO_18") (pintype "passive+no_connect"))
    )
    (net (code "79") (name "unconnected-(U7-GPIO0(MDC)-Pad48)") (class "Default")
      (node (ref "U7") (pin "48") (pinfunction "GPIO0(MDC)_48") (pintype "passive+no_connect"))
    )
    (net (code "80") (name "unconnected-(U7-GPIO1(MDIO)-Pad49)") (class "Default")
      (node (ref "U7") (pin "49") (pinfunction "GPIO1(MDIO)_49") (pintype "passive+no_connect"))
    )
    (net (code "81") (name "unconnected-(U7-GPIO2-Pad22)") (class "Default")
      (node (ref "U7") (pin "22") (pinfunction "GPIO2_22") (pintype "passive+no_connect"))
    )
    (net (code "82") (name "unconnected-(U7-GPIO15(1588_TOD)-Pad47)") (class "Default")
      (node (ref "U7") (pin "47") (pinfunction "GPIO15(1588_TOD)_47") (pintype "passive+no_connect"))
    )
    (net (code "83") (name "unconnected-(U7-LX-Pad60)") (class "Default")
      (node (ref "U7") (pin "60") (pinfunction "LX_60") (pintype "passive+no_connect"))
    )
  )
)
